# Debug_connector.net
KiCad netlist of a schematic drawn in Altium Designer
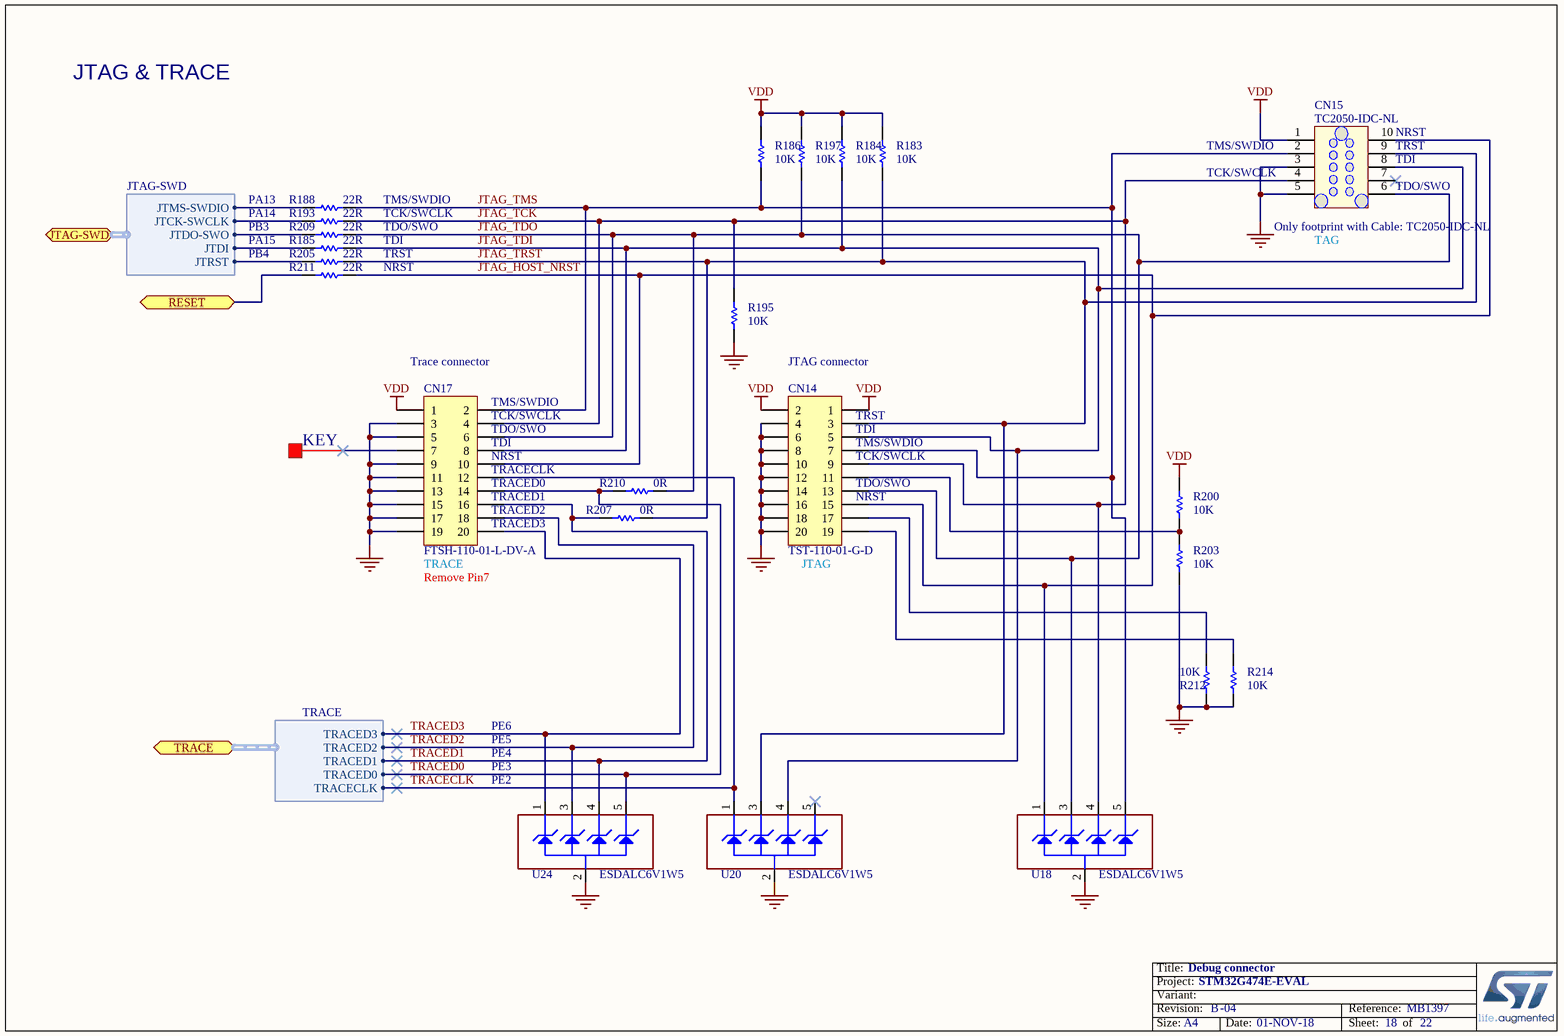
[diagram p0: Debug connector.SchDoc]

(export (version "E")
  (design (tool "Eeschema 10.0.6"))
  (components
    (comp (ref "CN14")
      (value "TST-110-01-G-D")
      (footprint "CON_CVILUX_CH87-20-2-V-1-00")
      (description "Header, 2.54mm, 10x2, VR, TH, Height 9.1mm/3,1mm")
      (fields
        (field (name "INTERNAL_PART_NUMBER") "MCD-01058")
        (field (name "MANUFACTURER") "SAMTEC")
        (field (name "PROVIDED_BY") "SUBCO")
      )
      (libsource (lib "") (part "Header 10x2_1"))
    )
    (comp (ref "CN15")
      (value "TC2050-IDC-NL")
      (footprint "CON_TAG-C_TC2050-IDC-NL")
      (description "Tag_Connector Header, 10x2, No legs")
      (fields
        (field (name "INTERNAL_PART_NUMBER") "MCD-00031")
        (field (name "MANUFACTURER_PART_NUMBER") "TC2050-IDC-NL-FP")
        (field (name "PROVIDED_BY") "SUBCO")
      )
      (libsource (lib "MCD_PARTS_database") (part "Tag-10-C"))
    )
    (comp (ref "CN17")
      (value "FTSH-110-01-L-DV-A")
      (footprint "CON_SAMTEC_FTSH-110-01-L-DV-A")
      (description "Header 10x2, 1.27mm, VR, CMS, Height 3.05mm with alignment pin")
      (fields
        (field (name "INTERNAL_PART_NUMBER") "MCD-01561")
        (field (name "MANUFACTURER") "SAMTEC")
        (field (name "PROVIDED_BY") "SUBCO")
      )
      (libsource (lib "MCD_PARTS_database") (part "Header 10x2"))
    )
    (comp (ref "R183")
      (value "10K")
      (footprint "R0402")
      (description "Resistor,10K,0402,1%,1/16W")
      (fields
        (field (name "INTERNAL_PART_NUMBER") "MCD-00053")
        (field (name "MANUFACTURER_PART_NUMBER") "RC0402FR-0710KL")
        (field (name "PROVIDED_BY") "SUBCO")
      )
      (libsource (lib "MCD_PARTS_database") (part "Resistor"))
    )
    (comp (ref "R184")
      (value "10K")
      (footprint "R0402")
      (description "Resistor,10K,0402,1%,1/16W")
      (fields
        (field (name "INTERNAL_PART_NUMBER") "MCD-00053")
        (field (name "MANUFACTURER_PART_NUMBER") "RC0402FR-0710KL")
        (field (name "PROVIDED_BY") "SUBCO")
      )
      (libsource (lib "MCD_PARTS_database") (part "Resistor"))
    )
    (comp (ref "R185")
      (value "22R")
      (footprint "R0402")
      (description "Resistor,22R,0402,1%,1/16W")
      (fields
        (field (name "INTERNAL_PART_NUMBER") "MCD-00189")
        (field (name "MANUFACTURER_PART_NUMBER") "RC0402FR-0722RL")
        (field (name "PROVIDED_BY") "SUBCO")
      )
      (libsource (lib "MCD_PARTS_database") (part "Resistor"))
    )
    (comp (ref "R186")
      (value "10K")
      (footprint "R0402")
      (description "Resistor,10K,0402,1%,1/16W")
      (fields
        (field (name "INTERNAL_PART_NUMBER") "MCD-00053")
        (field (name "MANUFACTURER_PART_NUMBER") "RC0402FR-0710KL")
        (field (name "PROVIDED_BY") "SUBCO")
      )
      (libsource (lib "MCD_PARTS_database") (part "Resistor"))
    )
    (comp (ref "R188")
      (value "22R")
      (footprint "R0402")
      (description "Resistor,22R,0402,1%,1/16W")
      (fields
        (field (name "INTERNAL_PART_NUMBER") "MCD-00189")
        (field (name "MANUFACTURER_PART_NUMBER") "RC0402FR-0722RL")
        (field (name "PROVIDED_BY") "SUBCO")
      )
      (libsource (lib "MCD_PARTS_database") (part "Resistor"))
    )
    (comp (ref "R193")
      (value "22R")
      (footprint "R0402")
      (description "Resistor,22R,0402,1%,1/16W")
      (fields
        (field (name "INTERNAL_PART_NUMBER") "MCD-00189")
        (field (name "MANUFACTURER_PART_NUMBER") "RC0402FR-0722RL")
        (field (name "PROVIDED_BY") "SUBCO")
      )
      (libsource (lib "MCD_PARTS_database") (part "Resistor"))
    )
    (comp (ref "R195")
      (value "10K")
      (footprint "R0402")
      (description "Resistor,10K,0402,1%,1/16W")
      (fields
        (field (name "INTERNAL_PART_NUMBER") "MCD-00053")
        (field (name "MANUFACTURER_PART_NUMBER") "RC0402FR-0710KL")
        (field (name "PROVIDED_BY") "SUBCO")
      )
      (libsource (lib "MCD_PARTS_database") (part "Resistor"))
    )
    (comp (ref "R197")
      (value "10K")
      (footprint "R0402")
      (description "Resistor,10K,0402,1%,1/16W")
      (fields
        (field (name "INTERNAL_PART_NUMBER") "MCD-00053")
        (field (name "MANUFACTURER_PART_NUMBER") "RC0402FR-0710KL")
        (field (name "PROVIDED_BY") "SUBCO")
      )
      (libsource (lib "MCD_PARTS_database") (part "Resistor"))
    )
    (comp (ref "R200")
      (value "10K")
      (footprint "R0402")
      (description "Resistor,10K,0402,1%,1/16W")
      (fields
        (field (name "INTERNAL_PART_NUMBER") "MCD-00053")
        (field (name "MANUFACTURER_PART_NUMBER") "RC0402FR-0710KL")
        (field (name "PROVIDED_BY") "SUBCO")
      )
      (libsource (lib "MCD_PARTS_database") (part "Resistor"))
    )
    (comp (ref "R203")
      (value "10K")
      (footprint "R0402")
      (description "Resistor,10K,0402,1%,1/16W")
      (fields
        (field (name "INTERNAL_PART_NUMBER") "MCD-00053")
        (field (name "MANUFACTURER_PART_NUMBER") "RC0402FR-0710KL")
        (field (name "PROVIDED_BY") "SUBCO")
      )
      (libsource (lib "MCD_PARTS_database") (part "Resistor"))
    )
    (comp (ref "R205")
      (value "22R")
      (footprint "R0402")
      (description "Resistor,22R,0402,1%,1/16W")
      (fields
        (field (name "INTERNAL_PART_NUMBER") "MCD-00189")
        (field (name "MANUFACTURER_PART_NUMBER") "RC0402FR-0722RL")
        (field (name "PROVIDED_BY") "SUBCO")
      )
      (libsource (lib "MCD_PARTS_database") (part "Resistor"))
    )
    (comp (ref "R207")
      (value "0R")
      (footprint "R0402")
      (description "Resistor,0R,0402,5%,1/16W")
      (fields
        (field (name "INTERNAL_PART_NUMBER") "MCD-00052")
        (field (name "MANUFACTURER_PART_NUMBER") "RC0402JR-070RL")
        (field (name "PROVIDED_BY") "SUBCO")
      )
      (libsource (lib "MCD_PARTS_database") (part "Resistor"))
    )
    (comp (ref "R209")
      (value "22R")
      (footprint "R0402")
      (description "Resistor,22R,0402,1%,1/16W")
      (fields
        (field (name "INTERNAL_PART_NUMBER") "MCD-00189")
        (field (name "MANUFACTURER_PART_NUMBER") "RC0402FR-0722RL")
        (field (name "PROVIDED_BY") "SUBCO")
      )
      (libsource (lib "MCD_PARTS_database") (part "Resistor"))
    )
    (comp (ref "R210")
      (value "0R")
      (footprint "R0402")
      (description "Resistor,0R,0402,5%,1/16W")
      (fields
        (field (name "INTERNAL_PART_NUMBER") "MCD-00052")
        (field (name "MANUFACTURER_PART_NUMBER") "RC0402JR-070RL")
        (field (name "PROVIDED_BY") "SUBCO")
      )
      (libsource (lib "MCD_PARTS_database") (part "Resistor"))
    )
    (comp (ref "R211")
      (value "22R")
      (footprint "R0402")
      (description "Resistor,22R,0402,1%,1/16W")
      (fields
        (field (name "INTERNAL_PART_NUMBER") "MCD-00189")
        (field (name "MANUFACTURER_PART_NUMBER") "RC0402FR-0722RL")
        (field (name "PROVIDED_BY") "SUBCO")
      )
      (libsource (lib "MCD_PARTS_database") (part "Resistor"))
    )
    (comp (ref "R212")
      (value "10K")
      (footprint "R0402")
      (description "Resistor,10K,0402,1%,1/16W")
      (fields
        (field (name "INTERNAL_PART_NUMBER") "MCD-00053")
        (field (name "MANUFACTURER_PART_NUMBER") "RC0402FR-0710KL")
        (field (name "PROVIDED_BY") "SUBCO")
      )
      (libsource (lib "MCD_PARTS_database") (part "Resistor"))
    )
    (comp (ref "R214")
      (value "10K")
      (footprint "R0402")
      (description "Resistor,10K,0402,1%,1/16W")
      (fields
        (field (name "INTERNAL_PART_NUMBER") "MCD-00053")
        (field (name "MANUFACTURER_PART_NUMBER") "RC0402FR-0710KL")
        (field (name "PROVIDED_BY") "SUBCO")
      )
      (libsource (lib "MCD_PARTS_database") (part "Resistor"))
    )
    (comp (ref "U18")
      (value "ESDALC6V1W5")
      (footprint "ESD_SOT323-5L")
      (description "Dual Transil array for ESD protection")
      (fields
        (field (name "INTERNAL_PART_NUMBER") "MCD-00136")
        (field (name "MANUFACTURER") "STMICROELECTRONICS")
        (field (name "PROVIDED_BY") "SUBCO with ST control")
      )
      (libsource (lib "MCD_PARTS_database") (part "ESDALC6V1W5"))
    )
    (comp (ref "U20")
      (value "ESDALC6V1W5")
      (footprint "ESD_SOT323-5L")
      (description "Dual Transil array for ESD protection")
      (fields
        (field (name "INTERNAL_PART_NUMBER") "MCD-00136")
        (field (name "MANUFACTURER") "STMICROELECTRONICS")
        (field (name "PROVIDED_BY") "SUBCO with ST control")
      )
      (libsource (lib "MCD_PARTS_database") (part "ESDALC6V1W5"))
    )
    (comp (ref "U24")
      (value "ESDALC6V1W5")
      (footprint "ESD_SOT323-5L")
      (description "Dual Transil array for ESD protection")
      (fields
        (field (name "INTERNAL_PART_NUMBER") "MCD-00136")
        (field (name "MANUFACTURER") "STMICROELECTRONICS")
        (field (name "PROVIDED_BY") "SUBCO with ST control")
      )
      (libsource (lib "MCD_PARTS_database") (part "ESDALC6V1W5"))
    )
  )
  (nets
    (net (code "3") (name "/JTAG_HOST_NRST") (class "Default")
      (node (ref "CN14") (pin "15") (pinfunction "15_15") (pintype "passive"))
      (node (ref "CN15") (pin "10") (pinfunction "10_10") (pintype "passive"))
      (node (ref "CN17") (pin "10") (pinfunction "10_10") (pintype "passive"))
      (node (ref "R211") (pin "1") (pinfunction "1_1") (pintype "passive"))
      (node (ref "U18") (pin "1") (pinfunction "IO1_1") (pintype "passive"))
    )
    (net (code "4") (name "/JTAG_TCK") (class "Default")
      (node (ref "CN14") (pin "9") (pinfunction "9_9") (pintype "passive"))
      (node (ref "CN15") (pin "4") (pinfunction "4_4") (pintype "passive"))
      (node (ref "CN17") (pin "4") (pinfunction "4_4") (pintype "passive"))
      (node (ref "R193") (pin "1") (pinfunction "1_1") (pintype "passive"))
      (node (ref "R195") (pin "2") (pinfunction "2_2") (pintype "passive"))
      (node (ref "U18") (pin "4") (pinfunction "IO3_4") (pintype "passive"))
    )
    (net (code "5") (name "/JTAG_TDI") (class "Default")
      (node (ref "CN14") (pin "5") (pinfunction "5_5") (pintype "passive"))
      (node (ref "CN15") (pin "8") (pinfunction "8_8") (pintype "passive"))
      (node (ref "CN17") (pin "8") (pinfunction "8_8") (pintype "passive"))
      (node (ref "R184") (pin "1") (pinfunction "1_1") (pintype "passive"))
      (node (ref "R185") (pin "1") (pinfunction "1_1") (pintype "passive"))
      (node (ref "U20") (pin "4") (pinfunction "IO3_4") (pintype "passive"))
    )
    (net (code "6") (name "/JTAG_TDO") (class "Default")
      (node (ref "CN14") (pin "13") (pinfunction "13_13") (pintype "passive"))
      (node (ref "CN15") (pin "6") (pinfunction "6_6") (pintype "passive"))
      (node (ref "CN17") (pin "6") (pinfunction "6_6") (pintype "passive"))
      (node (ref "R197") (pin "1") (pinfunction "1_1") (pintype "passive"))
      (node (ref "R209") (pin "1") (pinfunction "1_1") (pintype "passive"))
      (node (ref "R210") (pin "2") (pinfunction "2_2") (pintype "passive"))
      (node (ref "U18") (pin "3") (pinfunction "IO2_3") (pintype "passive"))
    )
    (net (code "7") (name "/JTAG_TMS") (class "Default")
      (node (ref "CN14") (pin "7") (pinfunction "7_7") (pintype "passive"))
      (node (ref "CN15") (pin "2") (pinfunction "2_2") (pintype "passive"))
      (node (ref "CN17") (pin "2") (pinfunction "2_2") (pintype "passive"))
      (node (ref "R186") (pin "1") (pinfunction "1_1") (pintype "passive"))
      (node (ref "R188") (pin "1") (pinfunction "1_1") (pintype "passive"))
      (node (ref "U18") (pin "5") (pinfunction "IO4_5") (pintype "passive"))
    )
    (net (code "8") (name "/JTAG_TRST") (class "Default")
      (node (ref "CN14") (pin "3") (pinfunction "3_3") (pintype "passive"))
      (node (ref "CN15") (pin "9") (pinfunction "9_9") (pintype "passive"))
      (node (ref "R183") (pin "1") (pinfunction "1_1") (pintype "passive"))
      (node (ref "R205") (pin "1") (pinfunction "1_1") (pintype "passive"))
      (node (ref "R207") (pin "2") (pinfunction "2_2") (pintype "passive"))
      (node (ref "U20") (pin "3") (pinfunction "IO2_3") (pintype "passive"))
    )
    (net (code "9") (name "/JTCK-SWCLK") (class "Default")
      (node (ref "R193") (pin "2") (pinfunction "2_2") (pintype "passive"))
    )
    (net (code "10") (name "/JTDI") (class "Default")
      (node (ref "R185") (pin "2") (pinfunction "2_2") (pintype "passive"))
    )
    (net (code "11") (name "/JTDO-SWO") (class "Default")
      (node (ref "R209") (pin "2") (pinfunction "2_2") (pintype "passive"))
    )
    (net (code "12") (name "/JTMS-SWDIO") (class "Default")
      (node (ref "R188") (pin "2") (pinfunction "2_2") (pintype "passive"))
    )
    (net (code "13") (name "/JTRST") (class "Default")
      (node (ref "R205") (pin "2") (pinfunction "2_2") (pintype "passive"))
    )
    (net (code "14") (name "/RESET") (class "Default")
      (node (ref "R211") (pin "2") (pinfunction "2_2") (pintype "passive"))
    )
    (net (code "15") (name "/TRACECLK") (class "Default")
      (node (ref "CN17") (pin "12") (pinfunction "12_12") (pintype "passive"))
      (node (ref "U20") (pin "1") (pinfunction "IO1_1") (pintype "passive"))
    )
    (net (code "16") (name "/TRACED0") (class "Default")
      (node (ref "CN17") (pin "14") (pinfunction "14_14") (pintype "passive"))
      (node (ref "R210") (pin "1") (pinfunction "1_1") (pintype "passive"))
      (node (ref "U24") (pin "5") (pinfunction "IO4_5") (pintype "passive"))
    )
    (net (code "17") (name "/TRACED1") (class "Default")
      (node (ref "CN17") (pin "16") (pinfunction "16_16") (pintype "passive"))
      (node (ref "R207") (pin "1") (pinfunction "1_1") (pintype "passive"))
      (node (ref "U24") (pin "4") (pinfunction "IO3_4") (pintype "passive"))
    )
    (net (code "18") (name "/TRACED2") (class "Default")
      (node (ref "CN17") (pin "18") (pinfunction "18_18") (pintype "passive"))
      (node (ref "U24") (pin "3") (pinfunction "IO2_3") (pintype "passive"))
    )
    (net (code "19") (name "/TRACED3") (class "Default")
      (node (ref "CN17") (pin "20") (pinfunction "20_20") (pintype "passive"))
      (node (ref "U24") (pin "1") (pinfunction "IO1_1") (pintype "passive"))
    )
    (net (code "22") (name "GND") (class "Default")
      (node (ref "CN14") (pin "10") (pinfunction "10_10") (pintype "passive"))
      (node (ref "CN14") (pin "12") (pinfunction "12_12") (pintype "passive"))
      (node (ref "CN14") (pin "14") (pinfunction "14_14") (pintype "passive"))
      (node (ref "CN14") (pin "16") (pinfunction "16_16") (pintype "passive"))
      (node (ref "CN14") (pin "18") (pinfunction "18_18") (pintype "passive"))
      (node (ref "CN14") (pin "20") (pinfunction "20_20") (pintype "passive"))
      (node (ref "CN14") (pin "4") (pinfunction "4_4") (pintype "passive"))
      (node (ref "CN14") (pin "6") (pinfunction "6_6") (pintype "passive"))
      (node (ref "CN14") (pin "8") (pinfunction "8_8") (pintype "passive"))
      (node (ref "CN15") (pin "3") (pinfunction "3_3") (pintype "passive"))
      (node (ref "CN15") (pin "5") (pinfunction "5_5") (pintype "passive"))
      (node (ref "CN17") (pin "11") (pinfunction "11_11") (pintype "passive"))
      (node (ref "CN17") (pin "13") (pinfunction "13_13") (pintype "passive"))
      (node (ref "CN17") (pin "15") (pinfunction "15_15") (pintype "passive"))
      (node (ref "CN17") (pin "17") (pinfunction "17_17") (pintype "passive"))
      (node (ref "CN17") (pin "19") (pinfunction "19_19") (pintype "passive"))
      (node (ref "CN17") (pin "3") (pinfunction "3_3") (pintype "passive"))
      (node (ref "CN17") (pin "5") (pinfunction "5_5") (pintype "passive"))
      (node (ref "CN17") (pin "9") (pinfunction "9_9") (pintype "passive"))
      (node (ref "R195") (pin "1") (pinfunction "1_1") (pintype "passive"))
      (node (ref "R203") (pin "1") (pinfunction "1_1") (pintype "passive"))
      (node (ref "R212") (pin "1") (pinfunction "1_1") (pintype "passive"))
      (node (ref "R214") (pin "1") (pinfunction "1_1") (pintype "passive"))
      (node (ref "U18") (pin "2") (pinfunction "GND_2") (pintype "passive"))
      (node (ref "U20") (pin "2") (pinfunction "GND_2") (pintype "passive"))
      (node (ref "U24") (pin "2") (pinfunction "GND_2") (pintype "passive"))
    )
    (net (code "23") (name "Net-(CN14-Pad11)") (class "Default")
      (node (ref "CN14") (pin "11") (pinfunction "11_11") (pintype "passive"))
      (node (ref "R200") (pin "1") (pinfunction "1_1") (pintype "passive"))
      (node (ref "R203") (pin "2") (pinfunction "2_2") (pintype "passive"))
    )
    (net (code "24") (name "Net-(CN14-Pad17)") (class "Default")
      (node (ref "CN14") (pin "17") (pinfunction "17_17") (pintype "passive"))
      (node (ref "R212") (pin "2") (pinfunction "2_2") (pintype "passive"))
    )
    (net (code "25") (name "Net-(CN14-Pad19)") (class "Default")
      (node (ref "CN14") (pin "19") (pinfunction "19_19") (pintype "passive"))
      (node (ref "R214") (pin "2") (pinfunction "2_2") (pintype "passive"))
    )
    (net (code "26") (name "VDD") (class "Default")
      (node (ref "CN14") (pin "1") (pinfunction "1_1") (pintype "passive"))
      (node (ref "CN14") (pin "2") (pinfunction "2_2") (pintype "passive"))
      (node (ref "CN15") (pin "1") (pinfunction "1_1") (pintype "passive"))
      (node (ref "CN17") (pin "1") (pinfunction "1_1") (pintype "passive"))
      (node (ref "R183") (pin "2") (pinfunction "2_2") (pintype "passive"))
      (node (ref "R184") (pin "2") (pinfunction "2_2") (pintype "passive"))
      (node (ref "R186") (pin "2") (pinfunction "2_2") (pintype "passive"))
      (node (ref "R197") (pin "2") (pinfunction "2_2") (pintype "passive"))
      (node (ref "R200") (pin "2") (pinfunction "2_2") (pintype "passive"))
    )
    (net (code "27") (name "unconnected-(CN15-Pad7)") (class "Default")
      (node (ref "CN15") (pin "7") (pinfunction "7_7") (pintype "passive+no_connect"))
    )
    (net (code "28") (name "unconnected-(CN17-Pad7)") (class "Default")
      (node (ref "CN17") (pin "7") (pinfunction "7_7") (pintype "passive+no_connect"))
    )
    (net (code "29") (name "unconnected-(U20-IO4-Pad5)") (class "Default")
      (node (ref "U20") (pin "5") (pinfunction "IO4_5") (pintype "passive+no_connect"))
    )
  )
)
